# Power_Monitor.net
KiCad netlist of a schematic drawn in Altium Designer
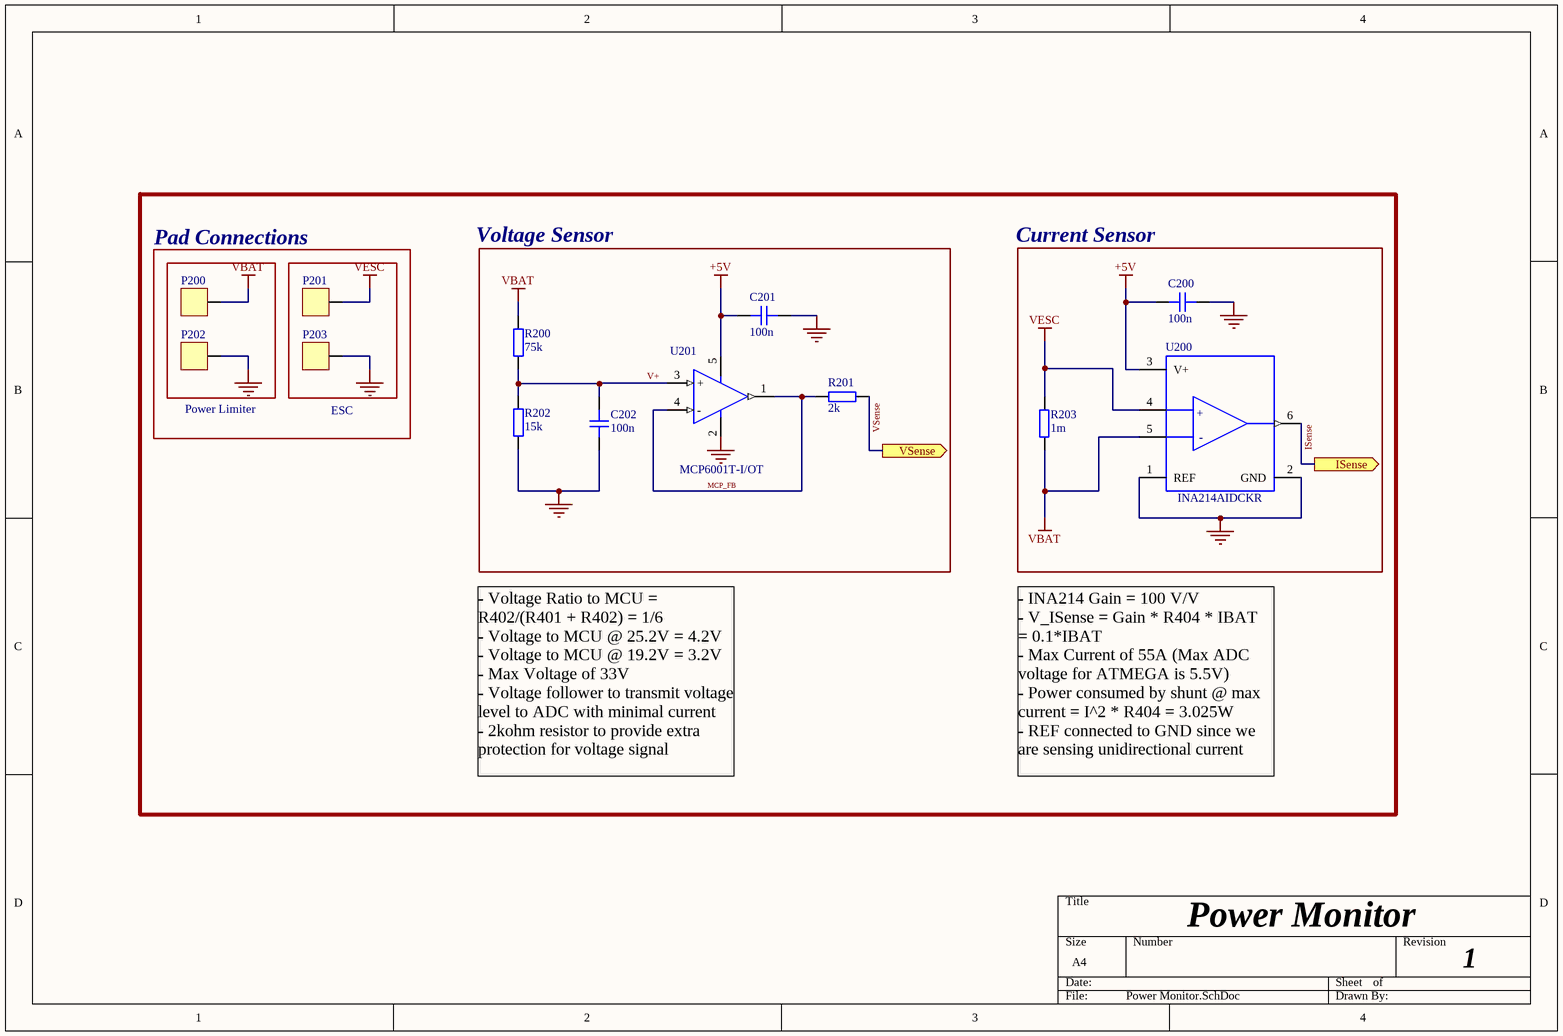
[diagram p0: Power Monitor.SchDoc]

(export (version "E")
  (design (tool "Eeschema 10.0.6"))
  (components
    (comp (ref "C200")
      (value "100n")
      (footprint "CAP_0603")
      (description "Capacitor SMD 0603")
      (libsource (lib "Footprint-Lib-PhilsLab") (part "CAP_0603"))
    )
    (comp (ref "C201")
      (value "100n")
      (footprint "CAP_0603")
      (description "Capacitor SMD 0603")
      (libsource (lib "Footprint-Lib-PhilsLab") (part "CAP_0603"))
    )
    (comp (ref "C202")
      (value "100n")
      (footprint "CAP_0603")
      (description "Capacitor SMD 0603")
      (libsource (lib "Footprint-Lib-PhilsLab") (part "CAP_0603"))
    )
    (comp (ref "P200")
      (value "6mm x 6mm Solder Pad")
      (footprint "6mm x 6mm Solder Pad")
      (libsource (lib "Sidharth's Schematic Library") (part "6mm x 6mm Solder Pad"))
    )
    (comp (ref "P201")
      (value "6mm x 6mm Solder Pad")
      (footprint "6mm x 6mm Solder Pad")
      (libsource (lib "Sidharth's Schematic Library") (part "6mm x 6mm Solder Pad"))
    )
    (comp (ref "P202")
      (value "6mm x 6mm Solder Pad")
      (footprint "6mm x 6mm Solder Pad")
      (libsource (lib "Sidharth's Schematic Library") (part "6mm x 6mm Solder Pad"))
    )
    (comp (ref "P203")
      (value "6mm x 6mm Solder Pad")
      (footprint "6mm x 6mm Solder Pad")
      (libsource (lib "Sidharth's Schematic Library") (part "6mm x 6mm Solder Pad"))
    )
    (comp (ref "R200")
      (value "75k")
      (footprint "RES_0603")
      (description "Resistor SMD 0603")
      (libsource (lib "Footprint-Lib-PhilsLab") (part "RES_0603"))
    )
    (comp (ref "R201")
      (value "2k")
      (footprint "RES_0603")
      (description "Resistor SMD 0603")
      (libsource (lib "Footprint-Lib-PhilsLab") (part "RES_0603"))
    )
    (comp (ref "R202")
      (value "15k")
      (footprint "RES_0603")
      (description "Resistor SMD 0603")
      (libsource (lib "Footprint-Lib-PhilsLab") (part "RES_0603"))
    )
    (comp (ref "R203")
      (value "1m")
      (footprint "EBWM2512F1L00S9")
      (fields
        (field (name "MANUFACTURER") "RESI")
        (field (name "MFR. PART NUMBER") "EBWM2512F1L00S9")
        (field (name "JLCPCB PART NUMBER") "C5224158")
      )
      (libsource (lib "Sidharth's Schematic Library") (part "EBWM2512F1L00S9"))
    )
    (comp (ref "U200")
      (value "INA214AIDCKR")
      (footprint "FP-DCK0006A-MFG")
      (description "IC CURRENT MONITOR 1% SC70-6 C105240")
      (fields
        (field (name "MANUFACTURER") "Texas Instruments")
        (field (name "OCTOPART") "https://octopart.com/ina214aidckr-texas+instruments-12190780")
      )
      (libsource (lib "Altium Content Vault") (part "8c207b95d72c4bf813034037ab452db"))
    )
    (comp (ref "U201")
      (value "MCP6001T-I/OT")
      (footprint "MCP6001-I/OT")
      (libsource (lib "Sidharth's Schematic Library") (part "MCP6001T-I/OT"))
    )
  )
  (nets
    (net (code "1") (name "+5V") (class "Default")
      (node (ref "C200") (pin "1") (pinfunction "1_1") (pintype "passive"))
      (node (ref "C201") (pin "1") (pinfunction "1_1") (pintype "passive"))
      (node (ref "U200") (pin "3") (pinfunction "V+_3") (pintype "power_in"))
      (node (ref "U201") (pin "5") (pinfunction "24_5") (pintype "passive"))
    )
    (net (code "2") (name "/ISense") (class "Default")
      (node (ref "U200") (pin "6") (pinfunction "VOUT_6") (pintype "output"))
    )
    (net (code "3") (name "/MCP_FB") (class "Default")
      (node (ref "R201") (pin "1") (pinfunction "1_1") (pintype "passive"))
      (node (ref "U201") (pin "1") (pinfunction "24_1") (pintype "output"))
      (node (ref "U201") (pin "4") (pinfunction "-_4") (pintype "input"))
    )
    (net (code "4") (name "/V+") (class "Default")
      (node (ref "C202") (pin "2") (pinfunction "2_2") (pintype "passive"))
      (node (ref "R200") (pin "2") (pinfunction "2_2") (pintype "passive"))
      (node (ref "R202") (pin "1") (pinfunction "1_1") (pintype "passive"))
      (node (ref "U201") (pin "3") (pinfunction "+_3") (pintype "input"))
    )
    (net (code "5") (name "/VSense") (class "Default")
      (node (ref "R201") (pin "2") (pinfunction "2_2") (pintype "passive"))
    )
    (net (code "6") (name "GND") (class "Default")
      (node (ref "C200") (pin "2") (pinfunction "2_2") (pintype "passive"))
      (node (ref "C201") (pin "2") (pinfunction "2_2") (pintype "passive"))
      (node (ref "C202") (pin "1") (pinfunction "1_1") (pintype "passive"))
      (node (ref "P202") (pin "1") (pinfunction "1_1") (pintype "passive"))
      (node (ref "P203") (pin "1") (pinfunction "1_1") (pintype "passive"))
      (node (ref "R202") (pin "2") (pinfunction "2_2") (pintype "passive"))
      (node (ref "U200") (pin "1") (pinfunction "REF_1") (pintype "passive"))
      (node (ref "U200") (pin "2") (pinfunction "GND_2") (pintype "power_in"))
      (node (ref "U201") (pin "2") (pinfunction "24_2") (pintype "passive"))
    )
    (net (code "7") (name "VBAT") (class "Default")
      (node (ref "P200") (pin "1") (pinfunction "1_1") (pintype "passive"))
      (node (ref "R200") (pin "1") (pinfunction "1_1") (pintype "passive"))
      (node (ref "R203") (pin "1") (pinfunction "1_1") (pintype "passive"))
      (node (ref "U200") (pin "5") (pinfunction "IN-_5") (pintype "tri_state"))
    )
    (net (code "8") (name "VESC") (class "Default")
      (node (ref "P201") (pin "1") (pinfunction "1_1") (pintype "passive"))
      (node (ref "R203") (pin "2") (pinfunction "2_2") (pintype "passive"))
      (node (ref "U200") (pin "4") (pinfunction "IN+_4") (pintype "tri_state"))
    )
  )
)
